# bg_power.net
KiCad netlist of a schematic drawn in Altium Designer
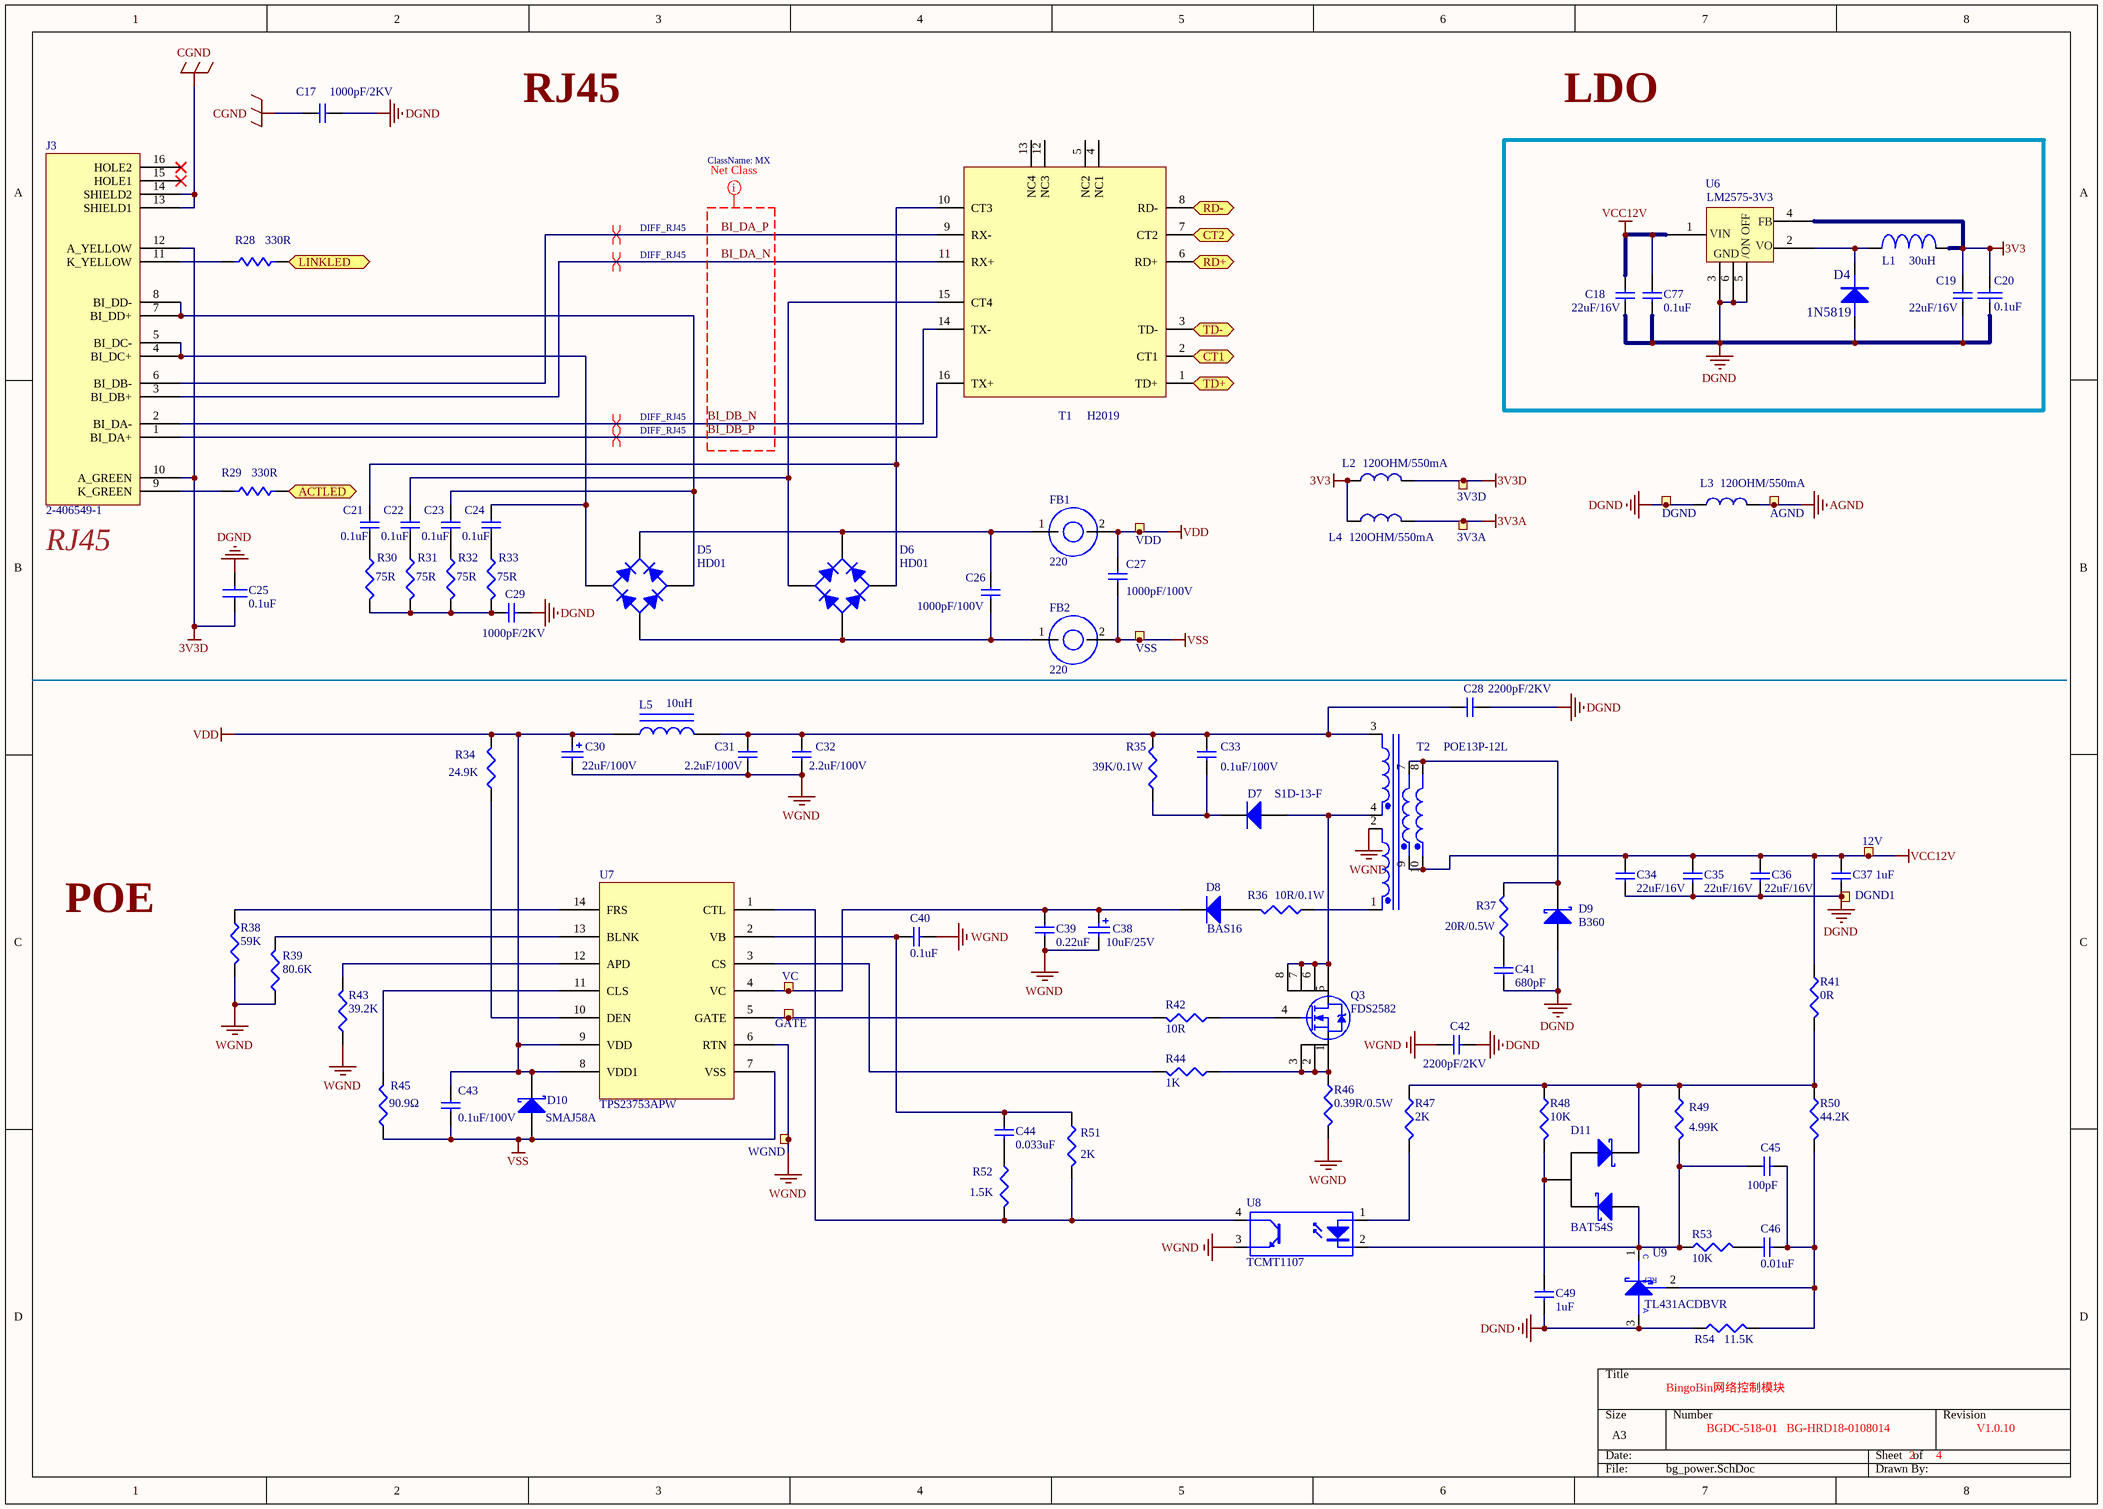
[diagram p0: bg_power.SchDoc]

(export (version "E")
  (design (tool "Eeschema 10.0.6"))
  (components
    (comp (ref "3V3A")
      (value "?.0mm,SMD")
      (footprint "TP_SMD_1_5mm")
      (description "1.0mm circular SMD testpad")
      (fields
        (field (name "PART NUMBER") "TP_SMD_?.0MM")
        (field (name "MANUFACTURER") "Nordic Semiconductor")
        (field (name "PUBLISHER") "Nordic Semiconductor")
      )
      (libsource (lib "") (part "TESTPAD_2"))
    )
    (comp (ref "3V3D")
      (value "?.0mm,SMD")
      (footprint "TP_SMD_1_5mm")
      (description "1.0mm circular SMD testpad")
      (fields
        (field (name "PART NUMBER") "TP_SMD_?.0MM")
        (field (name "MANUFACTURER") "Nordic Semiconductor")
        (field (name "PUBLISHER") "Nordic Semiconductor")
      )
      (libsource (lib "") (part "TESTPAD_2"))
    )
    (comp (ref "12V")
      (value "?.0mm,SMD")
      (footprint "TP_SMD_1_5mm")
      (description "1.0mm circular SMD testpad")
      (fields
        (field (name "PART NUMBER") "TP_SMD_?.0MM")
        (field (name "MANUFACTURER") "Nordic Semiconductor")
        (field (name "PUBLISHER") "Nordic Semiconductor")
      )
      (libsource (lib "bingo") (part "TESTPAD"))
    )
    (comp (ref "AGND")
      (value "?.0mm,SMD")
      (footprint "TP_SMD_1_5mm")
      (description "1.0mm circular SMD testpad")
      (fields
        (field (name "PART NUMBER") "TP_SMD_?.0MM")
        (field (name "MANUFACTURER") "Nordic Semiconductor")
        (field (name "PUBLISHER") "Nordic Semiconductor")
      )
      (libsource (lib "bingo") (part "TESTPAD"))
    )
    (comp (ref "C17")
      (value "1000pF/2KV")
      (footprint "1808")
      (description "Capacitor, Ceramic Chip,1000pF, 2KV, 10%,1808")
      (fields (field (name "PART NUMBER") "C0603-4µ7") (field (name "PUBLISHER") "Nordic Semiconductor"))
      (libsource (lib "sistalk") (part "CAP_0603"))
    )
    (comp (ref "C18")
      (value "22uF/16V")
      (footprint "C1210")
      (description "Capacitor, Ceramic, 22uF,16V, 10%,1210,X5R")
      (fields (field (name "PART NUMBER") "C0603-4µ7") (field (name "PUBLISHER") "Nordic Semiconductor"))
      (libsource (lib "sistalk") (part "CAP_0603"))
    )
    (comp (ref "C19")
      (value "22uF/16V")
      (footprint "C1210")
      (description "Capacitor, Ceramic, 22uF,16V, 10%,1210,X5R")
      (fields (field (name "PART NUMBER") "C0603-4µ7") (field (name "PUBLISHER") "Nordic Semiconductor"))
      (libsource (lib "sistalk") (part "CAP_0603"))
    )
    (comp (ref "C20")
      (value "0.1uF")
      (footprint "C0603")
      (description "Capacitor, Ceramic, 0.1uF, 16V, 10%, 0603, X7R")
      (libsource (lib "*") (part "CAP"))
    )
    (comp (ref "C21")
      (value "0.1uF")
      (footprint "C0603")
      (description "Capacitor, Ceramic, 0.1uF, 100V, 10%, 0603, X7R")
      (fields (field (name "PART NUMBER") "C0603-4µ7") (field (name "PUBLISHER") "Nordic Semiconductor"))
      (libsource (lib "sistalk") (part "CAP_0603"))
    )
    (comp (ref "C22")
      (value "0.1uF")
      (footprint "C0603")
      (description "Capacitor, Ceramic, 0.1uF, 100V, 10%, 0603, X7R")
      (fields (field (name "PART NUMBER") "C0603-4µ7") (field (name "PUBLISHER") "Nordic Semiconductor"))
      (libsource (lib "sistalk") (part "CAP_0603"))
    )
    (comp (ref "C23")
      (value "0.1uF")
      (footprint "C0603")
      (description "Capacitor, Ceramic, 0.1uF, 100V, 10%, 0603, X7R")
      (fields (field (name "PART NUMBER") "C0603-4µ7") (field (name "PUBLISHER") "Nordic Semiconductor"))
      (libsource (lib "sistalk") (part "CAP_0603"))
    )
    (comp (ref "C24")
      (value "0.1uF")
      (footprint "C0603")
      (description "Capacitor, Ceramic, 0.1uF, 100V, 10%, 0603, X7R")
      (fields (field (name "PART NUMBER") "C0603-4µ7") (field (name "PUBLISHER") "Nordic Semiconductor"))
      (libsource (lib "sistalk") (part "CAP_0603"))
    )
    (comp (ref "C25")
      (value "0.1uF")
      (footprint "C0603")
      (description "Capacitor, Ceramic, 0.1uF, 16V, 10%, 0603, X7R")
      (fields
        (field (name "MANUFACTURER") "TDK Corporation")
        (field (name "MANUFACTURER PART NUMBER") "C1005X5R1H104K")
      )
      (libsource (lib "Integrated_Library_RF_FEB_2012") (part "C1005X5R1H104K"))
    )
    (comp (ref "C26")
      (value "1000pF/100V")
      (footprint "0805")
      (description "Capacitor, Ceramic, 1000pF,100V, 10%,0805,X7R")
      (fields (field (name "PART NUMBER") "C0603-4µ7") (field (name "PUBLISHER") "Nordic Semiconductor"))
      (libsource (lib "sistalk") (part "CAP_0603"))
    )
    (comp (ref "C27")
      (value "1000pF/100V")
      (footprint "0805")
      (description "Capacitor, Ceramic, 1000pF,100V, 10%,0805,X7R")
      (fields (field (name "PART NUMBER") "C0603-4µ7") (field (name "PUBLISHER") "Nordic Semiconductor"))
      (libsource (lib "sistalk") (part "CAP_0603"))
    )
    (comp (ref "C28")
      (value "2200pF/2KV")
      (footprint "1812")
      (description "Capacitor, Ceramic, 2200pF,2KV, 20%,1812,X7R")
      (fields (field (name "PART NUMBER") "C0603-4µ7") (field (name "PUBLISHER") "Nordic Semiconductor"))
      (libsource (lib "sistalk") (part "CAP_0603"))
    )
    (comp (ref "C29")
      (value "1000pF/2KV")
      (footprint "1808")
      (description "Capacitor, Ceramic Chip,1000pF, 2KV, 10%,1808")
      (fields (field (name "PART NUMBER") "C0603-4µ7") (field (name "PUBLISHER") "Nordic Semiconductor"))
      (libsource (lib "sistalk") (part "CAP_0603"))
    )
    (comp (ref "C30")
      (value "22uF/100V")
      (footprint "C8*10.2mm")
      (description "Capacitor, Aluminum Electrolytic, 22uF,100V, 20%")
      (fields (field (name "PUBLISHER") "Altium Limited"))
      (libsource (lib "Miscellaneous Devices") (part "Cap Pol2"))
    )
    (comp (ref "C31")
      (value "2.2uF/100V")
      (footprint "C1210")
      (description "Capacitor, Ceramic, 2.2uF,100V, 10%,1210,X7R")
      (fields (field (name "PART NUMBER") "C0603-4µ7") (field (name "PUBLISHER") "Nordic Semiconductor"))
      (libsource (lib "sistalk") (part "CAP_0603"))
    )
    (comp (ref "C32")
      (value "2.2uF/100V")
      (footprint "C1210")
      (description "Capacitor, Ceramic, 2.2uF,100V, 10%,1210,X7R")
      (fields (field (name "PART NUMBER") "C0603-4µ7") (field (name "PUBLISHER") "Nordic Semiconductor"))
      (libsource (lib "sistalk") (part "CAP_0603"))
    )
    (comp (ref "C33")
      (value "0.1uF/100V")
      (footprint "0805")
      (description "Capacitor, Ceramic, 0.1uF,100V, 10%,0805,X7R")
      (fields (field (name "PART NUMBER") "C0603-4µ7") (field (name "PUBLISHER") "Nordic Semiconductor"))
      (libsource (lib "sistalk") (part "CAP_0603"))
    )
    (comp (ref "C34")
      (value "22uF/16V")
      (footprint "C1210")
      (description "Capacitor, Ceramic, 22uF,16V, 10%,1210,X5R")
      (fields (field (name "PART NUMBER") "C0603-4µ7") (field (name "PUBLISHER") "Nordic Semiconductor"))
      (libsource (lib "sistalk") (part "CAP_0603"))
    )
    (comp (ref "C35")
      (value "22uF/16V")
      (footprint "C1210")
      (description "Capacitor, Ceramic, 22uF,16V, 10%,1210,X5R")
      (fields (field (name "PART NUMBER") "C0603-4µ7") (field (name "PUBLISHER") "Nordic Semiconductor"))
      (libsource (lib "sistalk") (part "CAP_0603"))
    )
    (comp (ref "C36")
      (value "22uF/16V")
      (footprint "C1210")
      (description "Capacitor, Ceramic, 22uF,16V, 10%,1210,X5R")
      (fields (field (name "PART NUMBER") "C0603-4µ7") (field (name "PUBLISHER") "Nordic Semiconductor"))
      (libsource (lib "sistalk") (part "CAP_0603"))
    )
    (comp (ref "C37")
      (value "1uF")
      (footprint "C0603")
      (description "Capacitor, Ceramic, 1uF, 25V, 10%, 0603, X7R")
      (fields (field (name "PART NUMBER") "C0603-4µ7") (field (name "PUBLISHER") "Nordic Semiconductor"))
      (libsource (lib "sistalk") (part "CAP_0603"))
    )
    (comp (ref "C38")
      (value "10uF/25V")
      (footprint "C4*5.8")
      (description "Capacitor, Aluminum,10uF, 25V, 20%")
      (fields (field (name "PUBLISHER") "Altium Limited"))
      (libsource (lib "Miscellaneous Devices") (part "Cap Pol2"))
    )
    (comp (ref "C39")
      (value "0.22uF")
      (footprint "0805")
      (description "Capacitor, Ceramic, 0.22uF,25V, 10%,0805,X7R")
      (fields (field (name "PART NUMBER") "C0603-4µ7") (field (name "PUBLISHER") "Nordic Semiconductor"))
      (libsource (lib "sistalk") (part "CAP_0603"))
    )
    (comp (ref "C40")
      (value "0.1uF")
      (footprint "C0603")
      (description "Capacitor, Ceramic, 0.1uF, 16V, 10%, 0603, X7R")
      (fields (field (name "PART NUMBER") "C0603-4µ7") (field (name "PUBLISHER") "Nordic Semiconductor"))
      (libsource (lib "sistalk") (part "CAP_0603"))
    )
    (comp (ref "C41")
      (value "680pF")
      (footprint "0805")
      (description "Capacitor, Ceramic, 680pF,50V,5%,0805, NPO")
      (fields (field (name "PART NUMBER") "C0603-4µ7") (field (name "PUBLISHER") "Nordic Semiconductor"))
      (libsource (lib "sistalk") (part "CAP_0603"))
    )
    (comp (ref "C42")
      (value "2200pF/2KV")
      (footprint "1812")
      (description "Capacitor, Ceramic, 2200pF,2KV, 20%,1812,X7R")
      (fields (field (name "PART NUMBER") "C0603-4µ7") (field (name "PUBLISHER") "Nordic Semiconductor"))
      (libsource (lib "sistalk") (part "CAP_0603"))
    )
    (comp (ref "C43")
      (value "0.1uF/100V")
      (footprint "0805")
      (description "Capacitor, Ceramic, 0.1uF,100V, 10%,0805,X7R")
      (fields (field (name "PART NUMBER") "C0603-4µ7") (field (name "PUBLISHER") "Nordic Semiconductor"))
      (libsource (lib "sistalk") (part "CAP_0603"))
    )
    (comp (ref "C44")
      (value "0.033uF")
      (footprint "C0603")
      (description "Capacitor, Ceramic, 0.033uF, 50V, 10%, 0603, X7R")
      (fields (field (name "PART NUMBER") "C0603-4µ7") (field (name "PUBLISHER") "Nordic Semiconductor"))
      (libsource (lib "sistalk") (part "CAP_0603"))
    )
    (comp (ref "C45")
      (value "100pF")
      (footprint "C0603")
      (description "Capacitor, Ceramic, 100pF, 50V, 5%, 0603, X7R")
      (fields (field (name "PART NUMBER") "C0603-4µ7") (field (name "PUBLISHER") "Nordic Semiconductor"))
      (libsource (lib "sistalk") (part "CAP_0603"))
    )
    (comp (ref "C46")
      (value "0.01uF")
      (footprint "C0603")
      (description "Capacitor, Ceramic, 0.01uF, 50V, 10%, 0603, X7R")
      (fields (field (name "PART NUMBER") "C0603-4µ7") (field (name "PUBLISHER") "Nordic Semiconductor"))
      (libsource (lib "sistalk") (part "CAP_0603"))
    )
    (comp (ref "C49")
      (value "1uF")
      (footprint "C0603")
      (description "Capacitor, Ceramic, 1uF, 25V, 10%, 0603, X7R")
      (fields (field (name "PART NUMBER") "C0603-4µ7") (field (name "PUBLISHER") "Nordic Semiconductor"))
      (libsource (lib "sistalk") (part "CAP_0603"))
    )
    (comp (ref "C77")
      (value "0.1uF")
      (footprint "C0603")
      (description "Capacitor, X5R, ±10%")
      (fields (field (name "PART NUMBER") "C0603-4µ7") (field (name "PUBLISHER") "Nordic Semiconductor"))
      (libsource (lib "pca10028") (part "CAP_0603"))
    )
    (comp (ref "D4")
      (value "1N5819")
      (footprint "SOD123")
      (description "Diode Schottky, 40V,1A")
      (libsource (lib "*") (part "DIODE"))
    )
    (comp (ref "D5")
      (value "HD01")
      (footprint "HD01")
      (description "Bridge Rectifier, 100V, 0.8A, Glass Passivated, SMD")
      (fields (field (name "PUBLISHER") "Altium Limited"))
      (libsource (lib "Miscellaneous Devices") (part "Bridge1"))
    )
    (comp (ref "D6")
      (value "HD01")
      (footprint "HD01")
      (description "Bridge Rectifier, 100V, 0.8A, Glass Passivated, SMD")
      (fields (field (name "PUBLISHER") "Altium Limited"))
      (libsource (lib "Miscellaneous Devices") (part "Bridge1"))
    )
    (comp (ref "D7")
      (value "S1D-13-F")
      (footprint "SMA")
      (description "Diode, Rectifier, 1A, 200V")
      (fields (field (name "PUBLISHER") "Altium Limited"))
      (libsource (lib "Miscellaneous Devices") (part "Diode"))
    )
    (comp (ref "D8")
      (value "BAS16")
      (footprint "SOT-23")
      (description "Diode, Switching, 200mA, 75V, 225mW")
      (fields (field (name "PUBLISHER") "Altium Limited"))
      (libsource (lib "bingo") (part "BAS16"))
    )
    (comp (ref "D9")
      (value "B360")
      (footprint "SMC")
      (description "Diode Schottky, 60V, 3A, SMC")
      (fields (field (name "PUBLISHER") "Altium Limited"))
      (libsource (lib "Miscellaneous Devices") (part "D Schottky"))
    )
    (comp (ref "D10")
      (value "SMAJ58A")
      (footprint "SMB")
      (description "Diode,Transient Voltage Suppressor,400W,58V")
      (fields (field (name "PUBLISHER") "Altium Limited"))
      (libsource (lib "Miscellaneous Devices") (part "D Schottky"))
    )
    (comp (ref "D11")
      (value "BAT54S")
      (footprint "SOT-23")
      (description "Diode, Dual Schottky, 200mA, 30V")
      (fields (field (name "PUBLISHER") "Altium Limited"))
      (libsource (lib "bingo") (part "D Schottky"))
    )
    (comp (ref "DGND")
      (value "?.0mm,SMD")
      (footprint "TP_SMD_1_5mm")
      (description "1.0mm circular SMD testpad")
      (fields
        (field (name "PART NUMBER") "TP_SMD_?.0MM")
        (field (name "MANUFACTURER") "Nordic Semiconductor")
        (field (name "PUBLISHER") "Nordic Semiconductor")
      )
      (libsource (lib "bingo") (part "TESTPAD"))
    )
    (comp (ref "DGND1")
      (value "?.0mm,SMD")
      (footprint "TP_SMD_1_5mm")
      (description "1.0mm circular SMD testpad")
      (fields
        (field (name "PART NUMBER") "TP_SMD_?.0MM")
        (field (name "MANUFACTURER") "Nordic Semiconductor")
        (field (name "PUBLISHER") "Nordic Semiconductor")
      )
      (libsource (lib "") (part "TESTPAD_1"))
    )
    (comp (ref "FB1")
      (value "220")
      (footprint "0805")
      (description "Bead, Ferrite, SMT, 220 Ohms, 3A")
      (libsource (lib "bingo") (part "FB"))
    )
    (comp (ref "FB2")
      (value "220")
      (footprint "0805")
      (description "Bead, Ferrite, SMT, 220 Ohms, 3A")
      (libsource (lib "bingo") (part "FB"))
    )
    (comp (ref "GATE")
      (value "?.0mm,SMD")
      (footprint "TP_SMD_1mm")
      (description "1.0mm circular SMD testpad")
      (fields
        (field (name "PART NUMBER") "TP_SMD_?.0MM")
        (field (name "MANUFACTURER") "Nordic Semiconductor")
        (field (name "PUBLISHER") "Nordic Semiconductor")
      )
      (libsource (lib "bingo") (part "TESTPAD"))
    )
    (comp (ref "J3")
      (value "2-406549-1")
      (footprint "RJ45LED")
      (description "RJ45连接器/RJ45网口连接器,8p8c,90°,黄-绿LED灯,镀金,带屏蔽")
      (fields (field (name "MANUFACTURER") "Tyco"))
      (libsource (lib "Integrated_Library_RF_FEB_2012") (part "2-406549-1"))
    )
    (comp (ref "L1")
      (value "30uH")
      (footprint "L-7.5S")
      (description "330uH功率电感")
      (libsource (lib "*") (part "BEAD"))
    )
    (comp (ref "L2")
      (value "120OHM/550mA")
      (footprint "L0603")
      (description "Bead, Ferrite, SMT, 120 Ohms, 3A")
      (fields (field (name "TYPE") "120OHM/550mA"))
      (libsource (lib "bg_sch") (part "L0603"))
    )
    (comp (ref "L3")
      (value "120OHM/550mA")
      (footprint "L0603")
      (description "Bead, Ferrite, SMT, 120 Ohms, 3A")
      (fields (field (name "TYPE") "120OHM/550mA"))
      (libsource (lib "bg_sch") (part "L0603"))
    )
    (comp (ref "L4")
      (value "120OHM/550mA")
      (footprint "L0603")
      (description "Bead, Ferrite, SMT, 120 Ohms, 3A")
      (fields (field (name "TYPE") "120OHM/550mA"))
      (libsource (lib "bg_sch") (part "L0603"))
    )
    (comp (ref "L5")
      (value "10uH")
      (footprint "L4*4mm")
      (description "Inductor, SMT, 750mA, 350 milliohm,10uH")
      (fields (field (name "PUBLISHER") "Altium Limited"))
      (libsource (lib "Miscellaneous Devices") (part "Inductor Iron"))
    )
    (comp (ref "Q3")
      (value "FDS2582")
      (footprint "SO8")
      (description "MOSFET, N-ch, 150-V, 4.1A, 66 milliOhms")
      (fields (field (name "PUBLISHER") "Altium Limited"))
      (libsource (lib "bingo") (part "NMOS-2"))
    )
    (comp (ref "R28")
      (value "330R")
      (footprint "R0603")
      (description "RES, THICK FILM, 330 OHM, 5%, 1/10W, 0603")
      (libsource (lib "bg_sch") (part "R0603"))
    )
    (comp (ref "R29")
      (value "330R")
      (footprint "R0603")
      (description "RES, THICK FILM, 330 OHM, 5%, 1/10W, 0603")
      (libsource (lib "bg_sch") (part "R0603"))
    )
    (comp (ref "R30")
      (value "75R")
      (footprint "R0603")
      (description "RES, THICK FILM, 75 OHM, 1%, 1/10W, 0603")
      (fields (field (name "PUBLISHER") "Altium Limited"))
      (libsource (lib "Miscellaneous Devices") (part "Res3"))
    )
    (comp (ref "R31")
      (value "75R")
      (footprint "R0603")
      (description "RES, THICK FILM, 75 OHM, 1%, 1/10W, 0603")
      (fields (field (name "PUBLISHER") "Altium Limited"))
      (libsource (lib "Miscellaneous Devices") (part "Res3"))
    )
    (comp (ref "R32")
      (value "75R")
      (footprint "R0603")
      (description "RES, THICK FILM, 75 OHM, 1%, 1/10W, 0603")
      (fields (field (name "PUBLISHER") "Altium Limited"))
      (libsource (lib "Miscellaneous Devices") (part "Res3"))
    )
    (comp (ref "R33")
      (value "75R")
      (footprint "R0603")
      (description "RES, THICK FILM, 75 OHM, 1%, 1/10W, 0603")
      (fields (field (name "PUBLISHER") "Altium Limited"))
      (libsource (lib "Miscellaneous Devices") (part "Res3"))
    )
    (comp (ref "R34")
      (value "24.9K")
      (footprint "R0603")
      (description "RES, THICK FILM, 24.9K, 1%, 1/10W, 0603")
      (fields (field (name "PUBLISHER") "Altium Limited"))
      (libsource (lib "Miscellaneous Devices") (part "Res3"))
    )
    (comp (ref "R35")
      (value "39K/0.1W")
      (footprint "0805")
      (description "RES, THICK FILM, 39K, 1%, 1/8W, 0805")
      (fields (field (name "PUBLISHER") "Altium Limited"))
      (libsource (lib "Miscellaneous Devices") (part "Res3"))
    )
    (comp (ref "R36")
      (value "10R/0.1W")
      (footprint "0805")
      (description "RES, THICK FILM, 10 OHM, 1%, 1/8W, 0805")
      (fields (field (name "PUBLISHER") "Altium Limited"))
      (libsource (lib "Miscellaneous Devices") (part "Res3"))
    )
    (comp (ref "R37")
      (value "20R/0.5W")
      (footprint "2010")
      (description "RES, THICK FILM, 20 OHM, 5%, 1/2W, 2010")
      (fields (field (name "PUBLISHER") "Altium Limited"))
      (libsource (lib "Miscellaneous Devices") (part "Res3"))
    )
    (comp (ref "R38")
      (value "59K")
      (footprint "R0603")
      (description "RES, THICK FILM, 59K, 1%, 1/10W, 0603")
      (fields (field (name "PUBLISHER") "Altium Limited"))
      (libsource (lib "Miscellaneous Devices") (part "Res3"))
    )
    (comp (ref "R39")
      (value "80.6K")
      (footprint "R0603")
      (description "RES, THICK FILM, 80.6K, 1%, 1/10W, 0603")
      (fields (field (name "PUBLISHER") "Altium Limited"))
      (libsource (lib "Miscellaneous Devices") (part "Res3"))
    )
    (comp (ref "R41")
      (value "0R")
      (footprint "R0603")
      (description "RES, THICK FILM, 0 OHM, 1%, 1/10W, 0603")
      (fields (field (name "PUBLISHER") "Altium Limited"))
      (libsource (lib "Miscellaneous Devices") (part "Res3"))
    )
    (comp (ref "R42")
      (value "10R")
      (footprint "R0603")
      (description "RES, THICK FILM, 10 OHM, 5%, 1/10W, 0603")
      (fields (field (name "PUBLISHER") "Altium Limited"))
      (libsource (lib "Miscellaneous Devices") (part "Res3"))
    )
    (comp (ref "R43")
      (value "39.2K")
      (footprint "R0603")
      (description "RES, THICK FILM, 39.2K, 1%, 1/10W, 0603")
      (fields (field (name "PUBLISHER") "Altium Limited"))
      (libsource (lib "Miscellaneous Devices") (part "Res3"))
    )
    (comp (ref "R44")
      (value "1K")
      (footprint "R0603")
      (description "RES, THICK FILM, 1K, 5%, 1/10W, 0603")
      (fields (field (name "PUBLISHER") "Altium Limited"))
      (libsource (lib "Miscellaneous Devices") (part "Res3"))
    )
    (comp (ref "R45")
      (value "90.9Ω")
      (footprint "R0603")
      (description "RES, THICK FILM, 90.9 OHM, 1%, 1/10W, 0603")
      (fields (field (name "PUBLISHER") "Altium Limited"))
      (libsource (lib "Miscellaneous Devices") (part "Res3"))
    )
    (comp (ref "R46")
      (value "0.39R/0.5W")
      (footprint "1206")
      (description "RES, THICK FILM, 0.39 OHM, 1%, 3/4W, 2010")
      (fields (field (name "PUBLISHER") "Altium Limited"))
      (libsource (lib "Miscellaneous Devices") (part "Res3"))
    )
    (comp (ref "R47")
      (value "2K")
      (footprint "R0603")
      (description "RES, THICK FILM, 2K, 5%, 1/10W, 0603")
      (fields (field (name "PUBLISHER") "Altium Limited"))
      (libsource (lib "Miscellaneous Devices") (part "Res3"))
    )
    (comp (ref "R48")
      (value "10K")
      (footprint "R0603")
      (description "RES, THICK FILM, 10K, 5%, 1/10W, 0603")
      (fields (field (name "PUBLISHER") "Altium Limited"))
      (libsource (lib "Miscellaneous Devices") (part "Res3"))
    )
    (comp (ref "R49")
      (value "4.99K")
      (footprint "R0603")
      (description "RES, THICK FILM, 4.99K, 1%, 1/10W, 0603")
      (fields (field (name "PUBLISHER") "Altium Limited"))
      (libsource (lib "Miscellaneous Devices") (part "Res3"))
    )
    (comp (ref "R50")
      (value "44.2K")
      (footprint "R0603")
      (description "RES, THICK FILM, 44.2K, 1%, 1/10W, 0603")
      (fields (field (name "PUBLISHER") "Altium Limited"))
      (libsource (lib "Miscellaneous Devices") (part "Res3"))
    )
    (comp (ref "R51")
      (value "2K")
      (footprint "R0603")
      (description "RES, THICK FILM, 2K, 5%, 1/10W, 0603")
      (fields (field (name "PUBLISHER") "Altium Limited"))
      (libsource (lib "Miscellaneous Devices") (part "Res3"))
    )
    (comp (ref "R52")
      (value "1.5K")
      (footprint "R0603")
      (description "RES, THICK FILM, 1.5K, 5%, 1/10W, 0603")
      (fields (field (name "PUBLISHER") "Altium Limited"))
      (libsource (lib "Miscellaneous Devices") (part "Res3"))
    )
    (comp (ref "R53")
      (value "10K")
      (footprint "R0603")
      (description "RES, THICK FILM, 10K, 5%, 1/10W, 0603")
      (fields (field (name "PUBLISHER") "Altium Limited"))
      (libsource (lib "Miscellaneous Devices") (part "Res3"))
    )
    (comp (ref "R54")
      (value "11.5K")
      (footprint "R0603")
      (description "RES, THICK FILM, 11.5K, 1%, 1/10W, 0603")
      (fields (field (name "PUBLISHER") "Altium Limited"))
      (libsource (lib "Miscellaneous Devices") (part "Res3"))
    )
    (comp (ref "T1")
      (value "H2019")
      (footprint "H1102NL")
      (description "XFMR, 1000 Base-T, Ratio 1:1")
      (libsource (lib "bg_sch") (part "H1102NL"))
    )
    (comp (ref "T2")
      (value "POE13P-12L")
      (footprint "POE13P-12L")
      (description "Transformer, Flyback For PoE, 12V, 1A")
      (fields (field (name "PUBLISHER") "Altium Limited"))
      (libsource (lib "bingo") (part "Trans3"))
    )
    (comp (ref "U6")
      (value "LM2575-3V3")
      (footprint "TO-263-5")
      (description "SIMPLE SWITCHER® 1A Step-Down Voltage Regulator")
      (libsource (lib "*") (part "LM2575"))
    )
    (comp (ref "U7")
      (value "TPS23753APW")
      (footprint "TPS23753a")
      (description "IC, IEEE 802.3af Integrated Primary Side Controller")
      (libsource (lib "bingo") (part "TPS23753APW"))
    )
    (comp (ref "U8")
      (value "TCMT1107")
      (footprint "SSOP4")
      (description "IC, Photocoupler, 3750VRMS, 80-160% CTR")
      (fields (field (name "PUBLISHER") "Altium Limited"))
      (libsource (lib "Miscellaneous Devices") (part "Optoisolator1"))
    )
    (comp (ref "U9")
      (value "TL431ACDBVR")
      (footprint "SOT-23")
      (description "IC, Shunt Regulator, 2.5V Ref, 36V, 100mA, 1%")
      (fields
        (field (name "MANUFACTURER") "Texas Instruments")
        (field (name "MANUFACTURER PART NUMBER") "TL431AQDBZR")
        (field (name ".CHECKED PCB") "MM")
        (field (name ".CHECKED SCH") "MM")
        (field (name ".CREATOR") "MM")
      )
      (libsource (lib "OpenRex_V1I1") (part "TL431AQDBZR"))
    )
    (comp (ref "VC")
      (value "?.0mm,SMD")
      (footprint "TP_SMD_1mm")
      (description "1.0mm circular SMD testpad")
      (fields
        (field (name "PART NUMBER") "TP_SMD_?.0MM")
        (field (name "MANUFACTURER") "Nordic Semiconductor")
        (field (name "PUBLISHER") "Nordic Semiconductor")
      )
      (libsource (lib "bingo") (part "TESTPAD"))
    )
    (comp (ref "VDD")
      (value "?.0mm,SMD")
      (footprint "TP_SMD_1_5mm")
      (description "1.0mm circular SMD testpad")
      (fields
        (field (name "PART NUMBER") "TP_SMD_?.0MM")
        (field (name "MANUFACTURER") "Nordic Semiconductor")
        (field (name "PUBLISHER") "Nordic Semiconductor")
      )
      (libsource (lib "bingo") (part "TESTPAD"))
    )
    (comp (ref "VSS")
      (value "?.0mm,SMD")
      (footprint "TP_SMD_1_5mm")
      (description "1.0mm circular SMD testpad")
      (fields
        (field (name "PART NUMBER") "TP_SMD_?.0MM")
        (field (name "MANUFACTURER") "Nordic Semiconductor")
        (field (name "PUBLISHER") "Nordic Semiconductor")
      )
      (libsource (lib "bingo") (part "TESTPAD"))
    )
    (comp (ref "WGND")
      (value "?.0mm,SMD")
      (footprint "TP_SMD_1mm")
      (description "1.0mm circular SMD testpad")
      (fields
        (field (name "PART NUMBER") "TP_SMD_?.0MM")
        (field (name "MANUFACTURER") "Nordic Semiconductor")
        (field (name "PUBLISHER") "Nordic Semiconductor")
      )
      (libsource (lib "") (part "TESTPAD_3"))
    )
  )
  (nets
    (net (code "1") (name "/ACTLED") (class "Default")
      (node (ref "R29") (pin "2") (pinfunction "2_2") (pintype "passive"))
    )
    (net (code "2") (name "/BI_DA_N") (class "Default")
      (node (ref "J3") (pin "3") (pinfunction "BI_DB+_3") (pintype "passive"))
      (node (ref "T1") (pin "11") (pinfunction "RX+_11") (pintype "passive"))
    )
    (net (code "3") (name "/BI_DA_P") (class "Default")
      (node (ref "J3") (pin "6") (pinfunction "BI_DB-_6") (pintype "passive"))
      (node (ref "T1") (pin "9") (pinfunction "RX-_9") (pintype "passive"))
    )
    (net (code "4") (name "/BI_DB_N") (class "Default")
      (node (ref "J3") (pin "2") (pinfunction "BI_DA-_2") (pintype "passive"))
      (node (ref "T1") (pin "14") (pinfunction "TX-_14") (pintype "passive"))
    )
    (net (code "5") (name "/BI_DB_P") (class "Default")
      (node (ref "J3") (pin "1") (pinfunction "BI_DA+_1") (pintype "passive"))
      (node (ref "T1") (pin "16") (pinfunction "TX+_16") (pintype "passive"))
    )
    (net (code "6") (name "/CT1") (class "Default")
      (node (ref "T1") (pin "2") (pinfunction "CT1_2") (pintype "passive"))
    )
    (net (code "7") (name "/CT2") (class "Default")
      (node (ref "T1") (pin "7") (pinfunction "CT2_7") (pintype "passive"))
    )
    (net (code "8") (name "/LINKLED") (class "Default")
      (node (ref "R28") (pin "2") (pinfunction "2_2") (pintype "passive"))
    )
    (net (code "9") (name "/RD+") (class "Default")
      (node (ref "T1") (pin "6") (pinfunction "RD+_6") (pintype "passive"))
    )
    (net (code "10") (name "/RD-") (class "Default")
      (node (ref "T1") (pin "8") (pinfunction "RD-_8") (pintype "passive"))
    )
    (net (code "11") (name "/TD+") (class "Default")
      (node (ref "T1") (pin "1") (pinfunction "TD+_1") (pintype "passive"))
    )
    (net (code "12") (name "/TD-") (class "Default")
      (node (ref "T1") (pin "3") (pinfunction "TD-_3") (pintype "passive"))
    )
    (net (code "13") (name "3V3") (class "Default")
      (node (ref "C19") (pin "1") (pinfunction "1_1") (pintype "passive"))
      (node (ref "C20") (pin "1") (pinfunction "1_1") (pintype "passive"))
      (node (ref "L1") (pin "2") (pinfunction "2_2") (pintype "passive"))
      (node (ref "L2") (pin "1") (pinfunction "1_1") (pintype "passive"))
      (node (ref "L4") (pin "1") (pinfunction "1_1") (pintype "passive"))
      (node (ref "U6") (pin "4") (pinfunction "FEEDBACK_4") (pintype "passive"))
    )
    (net (code "14") (name "3V3A") (class "Default")
      (node (ref "3V3A") (pin "1") (pinfunction "1_1") (pintype "passive"))
      (node (ref "L4") (pin "2") (pinfunction "2_2") (pintype "passive"))
    )
    (net (code "15") (name "3V3D") (class "Default")
      (node (ref "3V3D") (pin "1") (pinfunction "1_1") (pintype "passive"))
      (node (ref "C25") (pin "1") (pinfunction "1_1") (pintype "passive"))
      (node (ref "J3") (pin "10") (pinfunction "A_GREEN_10") (pintype "passive"))
      (node (ref "J3") (pin "12") (pinfunction "A_YELLOW_12") (pintype "passive"))
      (node (ref "L2") (pin "2") (pinfunction "2_2") (pintype "passive"))
    )
    (net (code "16") (name "AGND") (class "Default")
      (node (ref "AGND") (pin "1") (pinfunction "1_1") (pintype "passive"))
      (node (ref "L3") (pin "2") (pinfunction "2_2") (pintype "passive"))
    )
    (net (code "17") (name "CGND") (class "Default")
      (node (ref "C17") (pin "2") (pinfunction "2_2") (pintype "passive"))
      (node (ref "J3") (pin "13") (pinfunction "SHIELD1_13") (pintype "passive"))
      (node (ref "J3") (pin "14") (pinfunction "SHIELD2_14") (pintype "passive"))
    )
    (net (code "18") (name "DGND") (class "Default")
      (node (ref "C17") (pin "1") (pinfunction "1_1") (pintype "passive"))
      (node (ref "C18") (pin "2") (pinfunction "2_2") (pintype "passive"))
      (node (ref "C19") (pin "2") (pinfunction "2_2") (pintype "passive"))
      (node (ref "C20") (pin "2") (pinfunction "2_2") (pintype "passive"))
      (node (ref "C25") (pin "2") (pinfunction "2_2") (pintype "passive"))
      (node (ref "C28") (pin "2") (pinfunction "2_2") (pintype "passive"))
      (node (ref "C29") (pin "1") (pinfunction "1_1") (pintype "passive"))
      (node (ref "C34") (pin "1") (pinfunction "1_1") (pintype "passive"))
      (node (ref "C35") (pin "1") (pinfunction "1_1") (pintype "passive"))
      (node (ref "C36") (pin "1") (pinfunction "1_1") (pintype "passive"))
      (node (ref "C37") (pin "1") (pinfunction "1_1") (pintype "passive"))
      (node (ref "C41") (pin "1") (pinfunction "1_1") (pintype "passive"))
      (node (ref "C42") (pin "2") (pinfunction "2_2") (pintype "passive"))
      (node (ref "C49") (pin "1") (pinfunction "1_1") (pintype "passive"))
      (node (ref "C77") (pin "2") (pinfunction "2_2") (pintype "passive"))
      (node (ref "D4") (pin "1") (pinfunction "A_1") (pintype "passive"))
      (node (ref "D9") (pin "1") (pinfunction "A_1") (pintype "passive"))
      (node (ref "DGND") (pin "1") (pinfunction "1_1") (pintype "passive"))
      (node (ref "DGND1") (pin "1") (pinfunction "1_1") (pintype "passive"))
      (node (ref "L3") (pin "1") (pinfunction "1_1") (pintype "passive"))
      (node (ref "R54") (pin "1") (pinfunction "1_1") (pintype "passive"))
      (node (ref "U6") (pin "3") (pinfunction "GND_3") (pintype "passive"))
      (node (ref "U6") (pin "5") (pinfunction "~{ON}/OFF_5") (pintype "passive"))
      (node (ref "U6") (pin "6") (pinfunction "6_6") (pintype "passive"))
      (node (ref "U9") (pin "3") (pinfunction "ANODE_3") (pintype "passive"))
    )
    (net (code "19") (name "Net-(C21-Pad1)") (class "Default")
      (node (ref "C21") (pin "1") (pinfunction "1_1") (pintype "passive"))
      (node (ref "R30") (pin "1") (pinfunction "1_1") (pintype "passive"))
    )
    (net (code "20") (name "Net-(C22-Pad1)") (class "Default")
      (node (ref "C22") (pin "1") (pinfunction "1_1") (pintype "passive"))
      (node (ref "R31") (pin "1") (pinfunction "1_1") (pintype "passive"))
    )
    (net (code "21") (name "Net-(C23-Pad1)") (class "Default")
      (node (ref "C23") (pin "1") (pinfunction "1_1") (pintype "passive"))
      (node (ref "R32") (pin "1") (pinfunction "1_1") (pintype "passive"))
    )
    (net (code "22") (name "Net-(C24-Pad1)") (class "Default")
      (node (ref "C24") (pin "1") (pinfunction "1_1") (pintype "passive"))
      (node (ref "R33") (pin "1") (pinfunction "1_1") (pintype "passive"))
    )
    (net (code "23") (name "Net-(C29-Pad2)") (class "Default")
      (node (ref "C29") (pin "2") (pinfunction "2_2") (pintype "passive"))
      (node (ref "R30") (pin "2") (pinfunction "2_2") (pintype "passive"))
      (node (ref "R31") (pin "2") (pinfunction "2_2") (pintype "passive"))
      (node (ref "R32") (pin "2") (pinfunction "2_2") (pintype "passive"))
      (node (ref "R33") (pin "2") (pinfunction "2_2") (pintype "passive"))
    )
    (net (code "24") (name "Net-(C41-Pad2)") (class "Default")
      (node (ref "C41") (pin "2") (pinfunction "2_2") (pintype "passive"))
      (node (ref "R37") (pin "1") (pinfunction "1_1") (pintype "passive"))
    )
    (net (code "25") (name "Net-(C44-Pad1)") (class "Default")
      (node (ref "C44") (pin "1") (pinfunction "1_1") (pintype "passive"))
      (node (ref "R52") (pin "1") (pinfunction "1_1") (pintype "passive"))
    )
    (net (code "26") (name "Net-(C46-Pad2)") (class "Default")
      (node (ref "C46") (pin "2") (pinfunction "2_2") (pintype "passive"))
      (node (ref "R53") (pin "2") (pinfunction "2_2") (pintype "passive"))
    )
    (net (code "27") (name "Net-(C49-Pad2)") (class "Default")
      (node (ref "C49") (pin "2") (pinfunction "2_2") (pintype "passive"))
      (node (ref "D11") (pin "3") (pinfunction "3_3") (pintype "passive"))
      (node (ref "R48") (pin "2") (pinfunction "2_2") (pintype "passive"))
    )
    (net (code "28") (name "Net-(D4-K)") (class "Default")
      (node (ref "D4") (pin "2") (pinfunction "K_2") (pintype "passive"))
      (node (ref "L1") (pin "1") (pinfunction "1_1") (pintype "passive"))
      (node (ref "U6") (pin "2") (pinfunction "OUTPU8T_2") (pintype "passive"))
    )
    (net (code "29") (name "Net-(D5-A)") (class "Default")
      (node (ref "C26") (pin "1") (pinfunction "1_1") (pintype "passive"))
      (node (ref "D5") (pin "3") (pinfunction "A_3") (pintype "passive"))
      (node (ref "D6") (pin "3") (pinfunction "A_3") (pintype "passive"))
      (node (ref "FB2") (pin "1") (pinfunction "1_1") (pintype "passive"))
    )
    (net (code "30") (name "Net-(D5-K)") (class "Default")
      (node (ref "C26") (pin "2") (pinfunction "2_2") (pintype "passive"))
      (node (ref "D5") (pin "1") (pinfunction "K_1") (pintype "passive"))
      (node (ref "D6") (pin "1") (pinfunction "K_1") (pintype "passive"))
      (node (ref "FB1") (pin "1") (pinfunction "1_1") (pintype "passive"))
    )
    (net (code "31") (name "Net-(D7-A)") (class "Default")
      (node (ref "D7") (pin "1") (pinfunction "A_1") (pintype "passive"))
      (node (ref "Q3") (pin "5") (pinfunction "D_5") (pintype "passive"))
      (node (ref "Q3") (pin "6") (pinfunction "6_6") (pintype "passive"))
      (node (ref "Q3") (pin "7") (pinfunction "7_7") (pintype "passive"))
      (node (ref "Q3") (pin "8") (pinfunction "8_8") (pintype "passive"))
      (node (ref "T2") (pin "4") (pinfunction "Sec2+_4") (pintype "passive"))
    )
    (net (code "32") (name "Net-(D7-K)") (class "Default")
      (node (ref "C33") (pin "1") (pinfunction "1_1") (pintype "passive"))
      (node (ref "D7") (pin "2") (pinfunction "K_2") (pintype "passive"))
      (node (ref "R35") (pin "1") (pinfunction "1_1") (pintype "passive"))
    )
    (net (code "33") (name "Net-(D8-A)") (class "Default")
      (node (ref "D8") (pin "1") (pinfunction "A_1") (pintype "passive"))
      (node (ref "R36") (pin "2") (pinfunction "2_2") (pintype "passive"))
    )
    (net (code "34") (name "Net-(D8-K)") (class "Default")
      (node (ref "C38") (pin "1") (pinfunction "1_1") (pintype "passive"))
      (node (ref "C39") (pin "2") (pinfunction "2_2") (pintype "passive"))
      (node (ref "D8") (pin "3") (pinfunction "K_3") (pintype "passive"))
      (node (ref "U7") (pin "4") (pinfunction "VC_4") (pintype "passive"))
      (node (ref "VC") (pin "1") (pinfunction "1_1") (pintype "passive"))
    )
    (net (code "35") (name "Net-(D9-K)") (class "Default")
      (node (ref "D9") (pin "2") (pinfunction "K_2") (pintype "passive"))
      (node (ref "R37") (pin "2") (pinfunction "2_2") (pintype "passive"))
      (node (ref "T2") (pin "7") (pinfunction "Pri-_7") (pintype "passive"))
      (node (ref "T2") (pin "8") (pinfunction "Pri-_8") (pintype "passive"))
    )
    (net (code "36") (name "Net-(D11-Pad2)") (class "Default")
      (node (ref "D11") (pin "2") (pinfunction "2_2") (pintype "passive"))
      (node (ref "R41") (pin "2") (pinfunction "2_2") (pintype "passive"))
      (node (ref "R47") (pin "1") (pinfunction "1_1") (pintype "passive"))
      (node (ref "R48") (pin "1") (pinfunction "1_1") (pintype "passive"))
      (node (ref "R49") (pin "1") (pinfunction "1_1") (pintype "passive"))
      (node (ref "R50") (pin "1") (pinfunction "1_1") (pintype "passive"))
    )
    (net (code "37") (name "Net-(J3-BI_DC+)") (class "Default")
      (node (ref "C24") (pin "2") (pinfunction "2_2") (pintype "passive"))
      (node (ref "D5") (pin "4") (pinfunction "C_4") (pintype "passive"))
      (node (ref "J3") (pin "4") (pinfunction "BI_DC+_4") (pintype "passive"))
      (node (ref "J3") (pin "5") (pinfunction "BI_DC-_5") (pintype "passive"))
    )
    (net (code "38") (name "Net-(J3-BI_DD+)") (class "Default")
      (node (ref "C23") (pin "2") (pinfunction "2_2") (pintype "passive"))
      (node (ref "D5") (pin "2") (pinfunction "C_2") (pintype "passive"))
      (node (ref "J3") (pin "7") (pinfunction "BI_DD+_7") (pintype "passive"))
      (node (ref "J3") (pin "8") (pinfunction "BI_DD-_8") (pintype "passive"))
    )
    (net (code "39") (name "Net-(J3-K_GREEN)") (class "Default")
      (node (ref "J3") (pin "9") (pinfunction "K_GREEN_9") (pintype "passive"))
      (node (ref "R29") (pin "1") (pinfunction "1_1") (pintype "passive"))
    )
    (net (code "40") (name "Net-(J3-K_YELLOW)") (class "Default")
      (node (ref "J3") (pin "11") (pinfunction "K_YELLOW_11") (pintype "passive"))
      (node (ref "R28") (pin "1") (pinfunction "1_1") (pintype "passive"))
    )
    (net (code "41") (name "Net-(Q3-10)") (class "Default")
      (node (ref "Q3") (pin "1") (pinfunction "S_1") (pintype "passive"))
      (node (ref "Q3") (pin "2") (pinfunction "9_2") (pintype "passive"))
      (node (ref "Q3") (pin "3") (pinfunction "10_3") (pintype "passive"))
      (node (ref "R44") (pin "1") (pinfunction "1_1") (pintype "passive"))
      (node (ref "R46") (pin "1") (pinfunction "1_1") (pintype "passive"))
    )
    (net (code "42") (name "Net-(Q3-G)") (class "Default")
      (node (ref "Q3") (pin "4") (pinfunction "G_4") (pintype "passive"))
      (node (ref "R42") (pin "1") (pinfunction "1_1") (pintype "passive"))
    )
    (net (code "43") (name "Net-(T1-CT3)") (class "Default")
      (node (ref "C21") (pin "2") (pinfunction "2_2") (pintype "passive"))
      (node (ref "D6") (pin "2") (pinfunction "C_2") (pintype "passive"))
      (node (ref "T1") (pin "10") (pinfunction "CT3_10") (pintype "passive"))
    )
    (net (code "44") (name "Net-(T1-CT4)") (class "Default")
      (node (ref "C22") (pin "2") (pinfunction "2_2") (pintype "passive"))
      (node (ref "D6") (pin "4") (pinfunction "C_4") (pintype "passive"))
      (node (ref "T1") (pin "15") (pinfunction "CT4_15") (pintype "passive"))
    )
    (net (code "45") (name "Net-(T2-Sec1+)") (class "Default")
      (node (ref "R36") (pin "1") (pinfunction "1_1") (pintype "passive"))
      (node (ref "T2") (pin "1") (pinfunction "Sec1+_1") (pintype "passive"))
    )
    (net (code "46") (name "Net-(T2-Sec2-)") (class "Default")
      (node (ref "C28") (pin "1") (pinfunction "1_1") (pintype "passive"))
      (node (ref "C31") (pin "2") (pinfunction "2_2") (pintype "passive"))
      (node (ref "C32") (pin "2") (pinfunction "2_2") (pintype "passive"))
      (node (ref "C33") (pin "2") (pinfunction "2_2") (pintype "passive"))
      (node (ref "L5") (pin "2") (pinfunction "2_2") (pintype "passive"))
      (node (ref "R35") (pin "2") (pinfunction "2_2") (pintype "passive"))
      (node (ref "T2") (pin "3") (pinfunction "Sec2-_3") (pintype "passive"))
    )
    (net (code "47") (name "Net-(U7-APD)") (class "Default")
      (node (ref "R43") (pin "2") (pinfunction "2_2") (pintype "passive"))
      (node (ref "U7") (pin "12") (pinfunction "APD_12") (pintype "passive"))
    )
    (net (code "48") (name "Net-(U7-BLNK)") (class "Default")
      (node (ref "R39") (pin "2") (pinfunction "2_2") (pintype "passive"))
      (node (ref "U7") (pin "13") (pinfunction "BLNK_13") (pintype "passive"))
    )
    (net (code "49") (name "Net-(U7-CLS)") (class "Default")
      (node (ref "R45") (pin "2") (pinfunction "2_2") (pintype "passive"))
      (node (ref "U7") (pin "11") (pinfunction "CLS_11") (pintype "passive"))
    )
    (net (code "50") (name "Net-(U7-CS)") (class "Default")
      (node (ref "R44") (pin "2") (pinfunction "2_2") (pintype "passive"))
      (node (ref "U7") (pin "3") (pinfunction "CS_3") (pintype "passive"))
    )
    (net (code "51") (name "Net-(U7-CTL)") (class "Default")
      (node (ref "R51") (pin "2") (pinfunction "2_2") (pintype "passive"))
      (node (ref "R52") (pin "2") (pinfunction "2_2") (pintype "passive"))
      (node (ref "U7") (pin "1") (pinfunction "CTL_1") (pintype "passive"))
      (node (ref "U8") (pin "4") (pinfunction "C_4") (pintype "passive"))
    )
    (net (code "52") (name "Net-(U7-DEN)") (class "Default")
      (node (ref "R34") (pin "1") (pinfunction "1_1") (pintype "passive"))
      (node (ref "U7") (pin "10") (pinfunction "DEN_10") (pintype "passive"))
    )
    (net (code "53") (name "Net-(U7-FRS)") (class "Default")
      (node (ref "R38") (pin "1") (pinfunction "1_1") (pintype "passive"))
      (node (ref "U7") (pin "14") (pinfunction "FRS_14") (pintype "passive"))
    )
    (net (code "54") (name "Net-(U7-GATE)") (class "Default")
      (node (ref "GATE") (pin "1") (pinfunction "1_1") (pintype "passive"))
      (node (ref "R42") (pin "2") (pinfunction "2_2") (pintype "passive"))
      (node (ref "U7") (pin "5") (pinfunction "GATE_5") (pintype "passive"))
    )
    (net (code "55") (name "Net-(U7-VB)") (class "Default")
      (node (ref "C40") (pin "2") (pinfunction "2_2") (pintype "passive"))
      (node (ref "C44") (pin "2") (pinfunction "2_2") (pintype "passive"))
      (node (ref "R51") (pin "1") (pinfunction "1_1") (pintype "passive"))
      (node (ref "U7") (pin "2") (pinfunction "VB_2") (pintype "passive"))
    )
    (net (code "56") (name "Net-(U8-A)") (class "Default")
      (node (ref "R47") (pin "2") (pinfunction "2_2") (pintype "passive"))
      (node (ref "U8") (pin "1") (pinfunction "A_1") (pintype "passive"))
    )
    (net (code "57") (name "Net-(U8-K)") (class "Default")
      (node (ref "C45") (pin "2") (pinfunction "2_2") (pintype "passive"))
      (node (ref "D11") (pin "1") (pinfunction "1_1") (pintype "passive"))
      (node (ref "R49") (pin "2") (pinfunction "2_2") (pintype "passive"))
      (node (ref "R53") (pin "1") (pinfunction "1_1") (pintype "passive"))
      (node (ref "U8") (pin "2") (pinfunction "K_2") (pintype "passive"))
      (node (ref "U9") (pin "1") (pinfunction "cathode_1") (pintype "passive"))
    )
    (net (code "58") (name "Net-(U9-REF)") (class "Default")
      (node (ref "C45") (pin "1") (pinfunction "1_1") (pintype "passive"))
      (node (ref "C46") (pin "1") (pinfunction "1_1") (pintype "passive"))
      (node (ref "R50") (pin "2") (pinfunction "2_2") (pintype "passive"))
      (node (ref "R54") (pin "2") (pinfunction "2_2") (pintype "passive"))
      (node (ref "U9") (pin "2") (pinfunction "REF_2") (pintype "passive"))
    )
    (net (code "59") (name "VCC12V") (class "Default")
      (node (ref "12V") (pin "1") (pinfunction "1_1") (pintype "passive"))
      (node (ref "C18") (pin "1") (pinfunction "1_1") (pintype "passive"))
      (node (ref "C34") (pin "2") (pinfunction "2_2") (pintype "passive"))
      (node (ref "C35") (pin "2") (pinfunction "2_2") (pintype "passive"))
      (node (ref "C36") (pin "2") (pinfunction "2_2") (pintype "passive"))
      (node (ref "C37") (pin "2") (pinfunction "2_2") (pintype "passive"))
      (node (ref "C77") (pin "1") (pinfunction "1_1") (pintype "passive"))
      (node (ref "R41") (pin "1") (pinfunction "1_1") (pintype "passive"))
      (node (ref "T2") (pin "10") (pinfunction "Pri+_10") (pintype "passive"))
      (node (ref "T2") (pin "9") (pinfunction "Pri+_9") (pintype "passive"))
      (node (ref "U6") (pin "1") (pinfunction "VIN_1") (pintype "passive"))
    )
    (net (code "60") (name "VDD") (class "Default")
      (node (ref "C27") (pin "2") (pinfunction "2_2") (pintype "passive"))
      (node (ref "C30") (pin "1") (pinfunction "1_1") (pintype "passive"))
      (node (ref "C43") (pin "2") (pinfunction "2_2") (pintype "passive"))
      (node (ref "D10") (pin "2") (pinfunction "K_2") (pintype "passive"))
      (node (ref "FB1") (pin "2") (pinfunction "2_2") (pintype "passive"))
      (node (ref "L5") (pin "1") (pinfunction "1_1") (pintype "passive"))
      (node (ref "R34") (pin "2") (pinfunction "2_2") (pintype "passive"))
      (node (ref "U7") (pin "8") (pinfunction "VDD1_8") (pintype "passive"))
      (node (ref "U7") (pin "9") (pinfunction "VDD_9") (pintype "passive"))
      (node (ref "VDD") (pin "1") (pinfunction "1_1") (pintype "passive"))
    )
    (net (code "61") (name "VSS") (class "Default")
      (node (ref "C27") (pin "1") (pinfunction "1_1") (pintype "passive"))
      (node (ref "C43") (pin "1") (pinfunction "1_1") (pintype "passive"))
      (node (ref "D10") (pin "1") (pinfunction "A_1") (pintype "passive"))
      (node (ref "FB2") (pin "2") (pinfunction "2_2") (pintype "passive"))
      (node (ref "R45") (pin "1") (pinfunction "1_1") (pintype "passive"))
      (node (ref "U7") (pin "7") (pinfunction "VSS_7") (pintype "passive"))
      (node (ref "VSS") (pin "1") (pinfunction "1_1") (pintype "passive"))
    )
    (net (code "62") (name "WGND") (class "Default")
      (node (ref "C30") (pin "2") (pinfunction "2_2") (pintype "passive"))
      (node (ref "C31") (pin "1") (pinfunction "1_1") (pintype "passive"))
      (node (ref "C32") (pin "1") (pinfunction "1_1") (pintype "passive"))
      (node (ref "C38") (pin "2") (pinfunction "2_2") (pintype "passive"))
      (node (ref "C39") (pin "1") (pinfunction "1_1") (pintype "passive"))
      (node (ref "C40") (pin "1") (pinfunction "1_1") (pintype "passive"))
      (node (ref "C42") (pin "1") (pinfunction "1_1") (pintype "passive"))
      (node (ref "R38") (pin "2") (pinfunction "2_2") (pintype "passive"))
      (node (ref "R39") (pin "1") (pinfunction "1_1") (pintype "passive"))
      (node (ref "R43") (pin "1") (pinfunction "1_1") (pintype "passive"))
      (node (ref "R46") (pin "2") (pinfunction "2_2") (pintype "passive"))
      (node (ref "T2") (pin "2") (pinfunction "Sec1-_2") (pintype "passive"))
      (node (ref "U7") (pin "6") (pinfunction "RTN_6") (pintype "passive"))
      (node (ref "U8") (pin "3") (pinfunction "E_3") (pintype "passive"))
      (node (ref "WGND") (pin "1") (pinfunction "1_1") (pintype "passive"))
    )
    (net (code "63") (name "unconnected-(J3-HOLE1-Pad15)") (class "Default")
      (node (ref "J3") (pin "15") (pinfunction "HOLE1_15") (pintype "passive+no_connect"))
    )
    (net (code "64") (name "unconnected-(J3-HOLE2-Pad16)") (class "Default")
      (node (ref "J3") (pin "16") (pinfunction "HOLE2_16") (pintype "passive+no_connect"))
    )
    (net (code "65") (name "unconnected-(T1-NC1-Pad4)") (class "Default")
      (node (ref "T1") (pin "4") (pinfunction "NC1_4") (pintype "passive"))
    )
    (net (code "66") (name "unconnected-(T1-NC2-Pad5)") (class "Default")
      (node (ref "T1") (pin "5") (pinfunction "NC2_5") (pintype "passive"))
    )
    (net (code "67") (name "unconnected-(T1-NC3-Pad12)") (class "Default")
      (node (ref "T1") (pin "12") (pinfunction "NC3_12") (pintype "passive"))
    )
    (net (code "68") (name "unconnected-(T1-NC4-Pad13)") (class "Default")
      (node (ref "T1") (pin "13") (pinfunction "NC4_13") (pintype "passive"))
    )
  )
)
